# Gorden.net
KiCad netlist of a schematic drawn in EAGLE
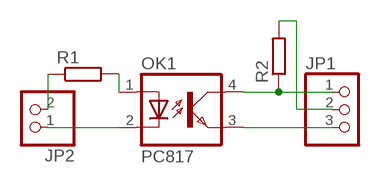
[diagram p0: schematic, sheet 1]

(export (version "E")
  (design (tool "Eeschema 10.0.6"))
  (components
    (comp (ref "JP1")
      (value "PINHD-1X3")
      (footprint "eagle-import:1X03")
      (libsource (lib "eagle-import") (part "PINHD-1X3"))
    )
    (comp (ref "JP2")
      (value "PINHD-1X2")
      (footprint "eagle-import:1X02")
      (libsource (lib "eagle-import") (part "PINHD-1X2"))
    )
    (comp (ref "OK1")
      (value "PC817")
      (footprint "eagle-import:DIL04")
      (fields (field (name "MPN") "PC817X4J000F"))
      (libsource (lib "eagle-import") (part "PC817"))
    )
    (comp (ref "R1")
      (value "R-EU_0204/7")
      (footprint "eagle-import:0204_7")
      (libsource (lib "eagle-import") (part "R-EU_0204/7"))
    )
    (comp (ref "R2")
      (value "R-EU_0204/7")
      (footprint "eagle-import:0204_7")
      (libsource (lib "eagle-import") (part "R-EU_0204/7"))
    )
  )
  (nets
    (net (code "1") (name "Net-(JP1-Pad2)") (class "Default")
      (node (ref "JP1") (pin "2") (pinfunction "2_2") (pintype "passive"))
      (node (ref "R2") (pin "2") (pinfunction "2_2") (pintype "passive"))
    )
    (net (code "2") (name "Net-(JP2-Pad2)") (class "Default")
      (node (ref "JP2") (pin "2") (pinfunction "2_2") (pintype "passive"))
      (node (ref "R1") (pin "1") (pinfunction "1_1") (pintype "passive"))
    )
    (net (code "3") (name "Net-(OK1-A)") (class "Default")
      (node (ref "OK1") (pin "1") (pinfunction "A_1") (pintype "passive"))
      (node (ref "R1") (pin "2") (pinfunction "2_2") (pintype "passive"))
    )
    (net (code "4") (name "Net-(OK1-C)") (class "Default")
      (node (ref "JP2") (pin "1") (pinfunction "1_1") (pintype "passive"))
      (node (ref "OK1") (pin "2") (pinfunction "C_2") (pintype "passive"))
    )
    (net (code "5") (name "Net-(OK1-COL)") (class "Default")
      (node (ref "JP1") (pin "1") (pinfunction "1_1") (pintype "passive"))
      (node (ref "OK1") (pin "4") (pinfunction "COL_4") (pintype "passive"))
      (node (ref "R2") (pin "1") (pinfunction "1_1") (pintype "passive"))
    )
    (net (code "6") (name "Net-(OK1-EMIT)") (class "Default")
      (node (ref "JP1") (pin "3") (pinfunction "3_3") (pintype "passive"))
      (node (ref "OK1") (pin "3") (pinfunction "EMIT_3") (pintype "passive"))
    )
  )
)
